# record.net
KiCad netlist of a schematic drawn in EAGLE
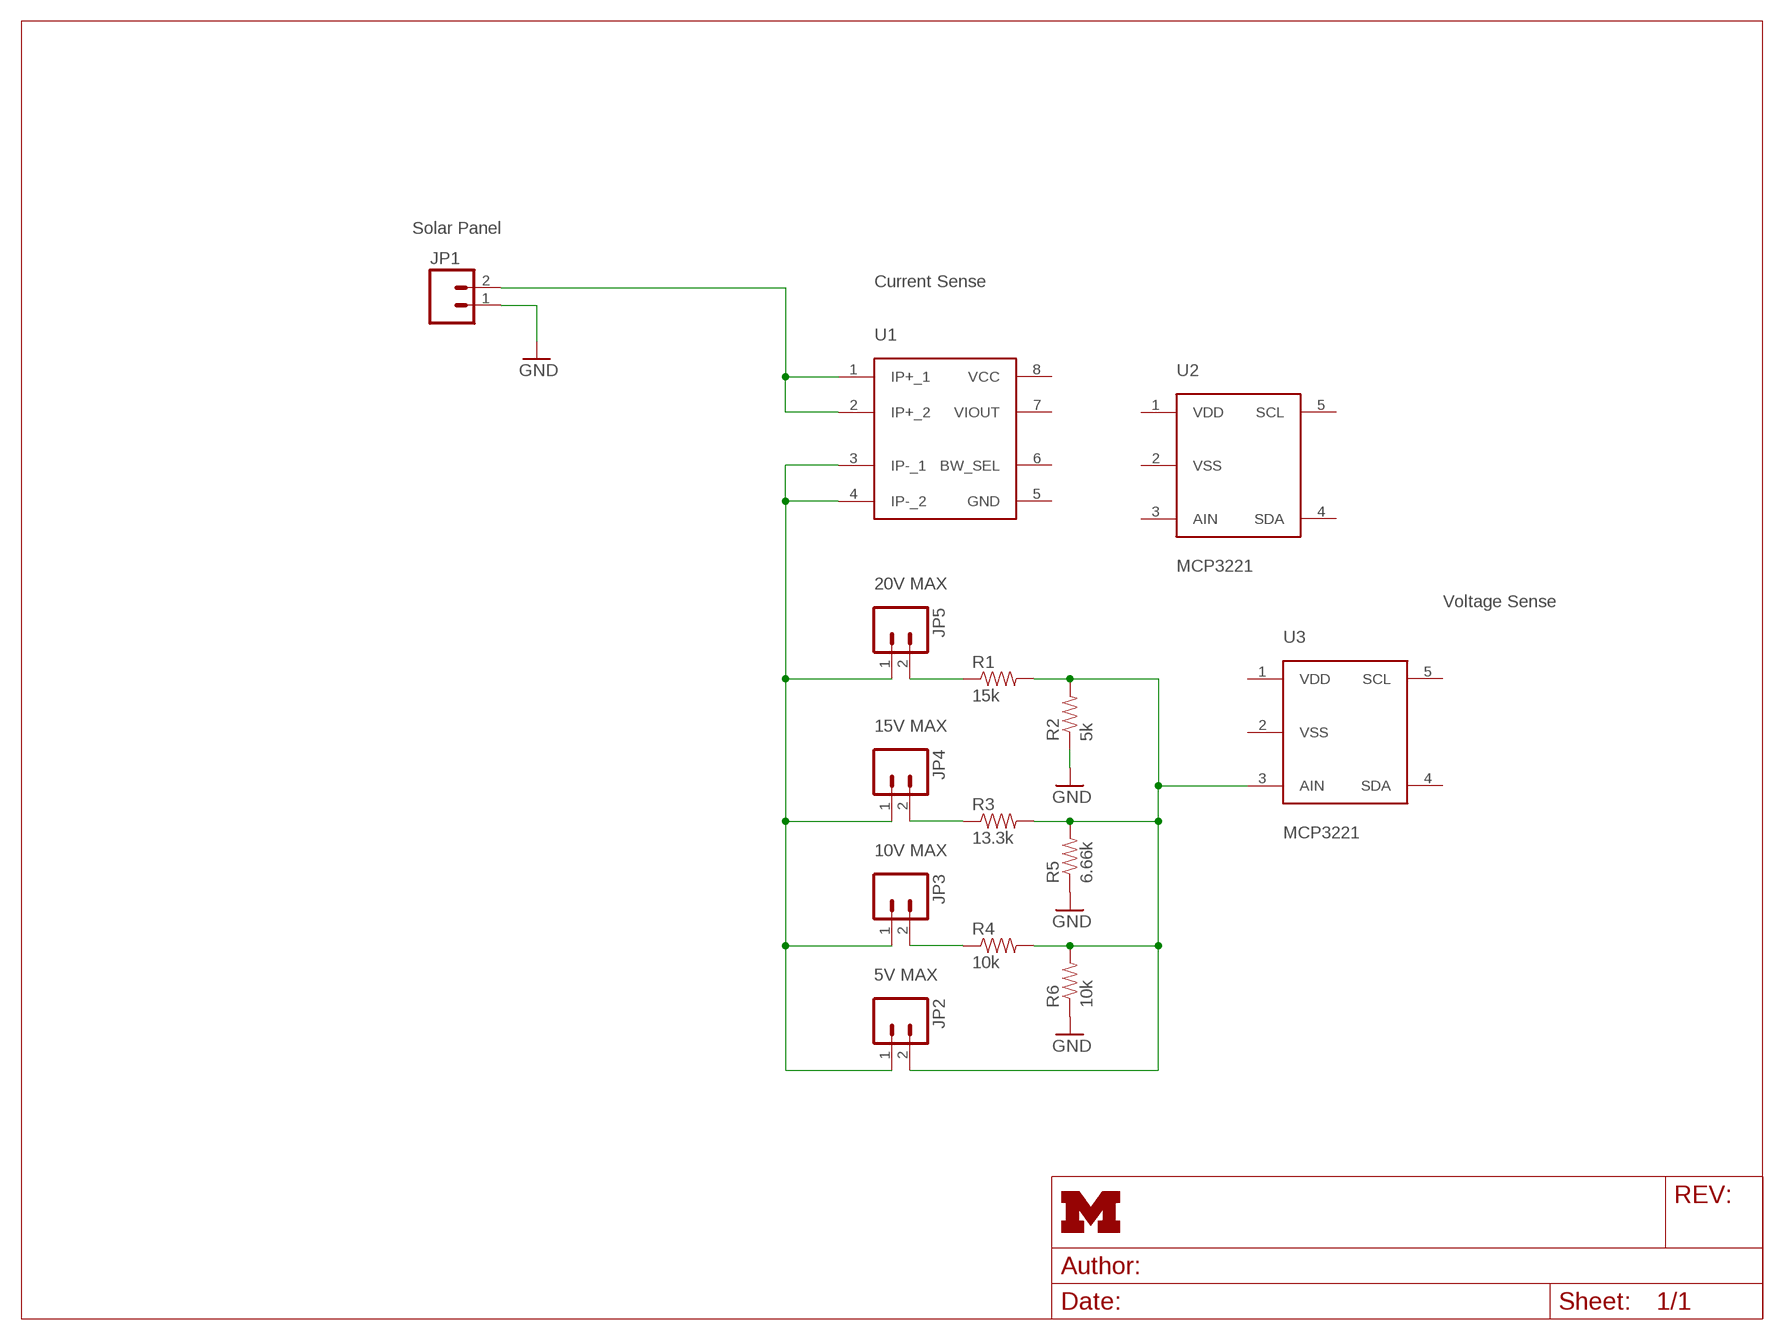
[diagram p0: schematic, sheet 1]

(export (version "E")
  (design (tool "Eeschema 10.0.6"))
  (components
    (comp (ref "JP1")
      (value "M02PTH")
      (footprint "eagle-import:1X02")
      (libsource (lib "eagle-import") (part "M02PTH"))
    )
    (comp (ref "JP2")
      (value "M02PTH")
      (footprint "eagle-import:1X02")
      (libsource (lib "eagle-import") (part "M02PTH"))
    )
    (comp (ref "JP3")
      (value "M02PTH")
      (footprint "eagle-import:1X02")
      (libsource (lib "eagle-import") (part "M02PTH"))
    )
    (comp (ref "JP4")
      (value "M02PTH")
      (footprint "eagle-import:1X02")
      (libsource (lib "eagle-import") (part "M02PTH"))
    )
    (comp (ref "JP5")
      (value "M02PTH")
      (footprint "eagle-import:1X02")
      (libsource (lib "eagle-import") (part "M02PTH"))
    )
    (comp (ref "R1")
      (value "15k")
      (footprint "eagle-import:0603-RES")
      (libsource (lib "eagle-import") (part "RESISTOR0603-RES"))
    )
    (comp (ref "R2")
      (value "5k")
      (footprint "eagle-import:0603-RES")
      (libsource (lib "eagle-import") (part "RESISTOR0603-RES"))
    )
    (comp (ref "R3")
      (value "13.3k")
      (footprint "eagle-import:0603-RES")
      (libsource (lib "eagle-import") (part "RESISTOR0603-RES"))
    )
    (comp (ref "R4")
      (value "10k")
      (footprint "eagle-import:0603-RES")
      (libsource (lib "eagle-import") (part "RESISTOR0603-RES"))
    )
    (comp (ref "R5")
      (value "6.66k")
      (footprint "eagle-import:0603-RES")
      (libsource (lib "eagle-import") (part "RESISTOR0603-RES"))
    )
    (comp (ref "R6")
      (value "10k")
      (footprint "eagle-import:0603-RES")
      (libsource (lib "eagle-import") (part "RESISTOR0603-RES"))
    )
    (comp (ref "U1")
      (value "ACS723")
      (footprint "eagle-import:SOIC-8")
      (libsource (lib "eagle-import") (part "ACS723"))
    )
    (comp (ref "U2")
      (value "MCP3221")
      (footprint "eagle-import:SOT-23-5")
      (libsource (lib "eagle-import") (part "MCP3221"))
    )
    (comp (ref "U3")
      (value "MCP3221")
      (footprint "eagle-import:SOT-23-5")
      (libsource (lib "eagle-import") (part "MCP3221"))
    )
  )
  (nets
    (net (code "1") (name "GND") (class "Default")
      (node (ref "JP1") (pin "1") (pinfunction "1_1") (pintype "passive"))
      (node (ref "R2") (pin "1") (pinfunction "1_1") (pintype "passive"))
      (node (ref "R5") (pin "1") (pinfunction "1_1") (pintype "passive"))
      (node (ref "R6") (pin "1") (pinfunction "1_1") (pintype "passive"))
    )
    (net (code "2") (name "Net-(JP3-Pad2)") (class "Default")
      (node (ref "JP3") (pin "2") (pinfunction "2_2") (pintype "passive"))
      (node (ref "R4") (pin "1") (pinfunction "1_1") (pintype "passive"))
    )
    (net (code "3") (name "Net-(JP4-Pad2)") (class "Default")
      (node (ref "JP4") (pin "2") (pinfunction "2_2") (pintype "passive"))
      (node (ref "R3") (pin "1") (pinfunction "1_1") (pintype "passive"))
    )
    (net (code "4") (name "Net-(JP5-Pad2)") (class "Default")
      (node (ref "JP5") (pin "2") (pinfunction "2_2") (pintype "passive"))
      (node (ref "R1") (pin "1") (pinfunction "1_1") (pintype "passive"))
    )
    (net (code "5") (name "Net-(U1-IP+_1)") (class "Default")
      (node (ref "JP1") (pin "2") (pinfunction "2_2") (pintype "passive"))
      (node (ref "U1") (pin "1") (pinfunction "IP+_1_1") (pintype "bidirectional"))
      (node (ref "U1") (pin "2") (pinfunction "IP+_2_2") (pintype "bidirectional"))
    )
    (net (code "6") (name "Net-(U1-IP-_1)") (class "Default")
      (node (ref "JP2") (pin "1") (pinfunction "1_1") (pintype "passive"))
      (node (ref "JP3") (pin "1") (pinfunction "1_1") (pintype "passive"))
      (node (ref "JP4") (pin "1") (pinfunction "1_1") (pintype "passive"))
      (node (ref "JP5") (pin "1") (pinfunction "1_1") (pintype "passive"))
      (node (ref "U1") (pin "3") (pinfunction "IP-_1_3") (pintype "bidirectional"))
      (node (ref "U1") (pin "4") (pinfunction "IP-_2_4") (pintype "bidirectional"))
    )
    (net (code "7") (name "Net-(U3-AIN)") (class "Default")
      (node (ref "JP2") (pin "2") (pinfunction "2_2") (pintype "passive"))
      (node (ref "R1") (pin "2") (pinfunction "2_2") (pintype "passive"))
      (node (ref "R2") (pin "2") (pinfunction "2_2") (pintype "passive"))
      (node (ref "R3") (pin "2") (pinfunction "2_2") (pintype "passive"))
      (node (ref "R4") (pin "2") (pinfunction "2_2") (pintype "passive"))
      (node (ref "R5") (pin "2") (pinfunction "2_2") (pintype "passive"))
      (node (ref "R6") (pin "2") (pinfunction "2_2") (pintype "passive"))
      (node (ref "U3") (pin "3") (pinfunction "AIN_3") (pintype "bidirectional"))
    )
    (net (code "8") (name "unconnected-(U1-BW_SEL-Pad6)") (class "Default")
      (node (ref "U1") (pin "6") (pinfunction "BW_SEL_6") (pintype "bidirectional"))
    )
    (net (code "9") (name "unconnected-(U1-GND-Pad5)") (class "Default")
      (node (ref "U1") (pin "5") (pinfunction "GND_5") (pintype "bidirectional"))
    )
    (net (code "10") (name "unconnected-(U1-VCC-Pad8)") (class "Default")
      (node (ref "U1") (pin "8") (pinfunction "VCC_8") (pintype "bidirectional"))
    )
    (net (code "11") (name "unconnected-(U1-VIOUT-Pad7)") (class "Default")
      (node (ref "U1") (pin "7") (pinfunction "VIOUT_7") (pintype "bidirectional"))
    )
    (net (code "12") (name "unconnected-(U2-AIN-Pad3)") (class "Default")
      (node (ref "U2") (pin "3") (pinfunction "AIN_3") (pintype "bidirectional"))
    )
    (net (code "13") (name "unconnected-(U2-SCL-Pad5)") (class "Default")
      (node (ref "U2") (pin "5") (pinfunction "SCL_5") (pintype "bidirectional"))
    )
    (net (code "14") (name "unconnected-(U2-SDA-Pad4)") (class "Default")
      (node (ref "U2") (pin "4") (pinfunction "SDA_4") (pintype "bidirectional"))
    )
    (net (code "15") (name "unconnected-(U2-VDD-Pad1)") (class "Default")
      (node (ref "U2") (pin "1") (pinfunction "VDD_1") (pintype "bidirectional"))
    )
    (net (code "16") (name "unconnected-(U2-VSS-Pad2)") (class "Default")
      (node (ref "U2") (pin "2") (pinfunction "VSS_2") (pintype "bidirectional"))
    )
    (net (code "17") (name "unconnected-(U3-SCL-Pad5)") (class "Default")
      (node (ref "U3") (pin "5") (pinfunction "SCL_5") (pintype "bidirectional"))
    )
    (net (code "18") (name "unconnected-(U3-SDA-Pad4)") (class "Default")
      (node (ref "U3") (pin "4") (pinfunction "SDA_4") (pintype "bidirectional"))
    )
    (net (code "19") (name "unconnected-(U3-VDD-Pad1)") (class "Default")
      (node (ref "U3") (pin "1") (pinfunction "VDD_1") (pintype "bidirectional"))
    )
    (net (code "20") (name "unconnected-(U3-VSS-Pad2)") (class "Default")
      (node (ref "U3") (pin "2") (pinfunction "VSS_2") (pintype "bidirectional"))
    )
  )
)
